# power-mcu.net
KiCad netlist of a schematic drawn in Altium Designer
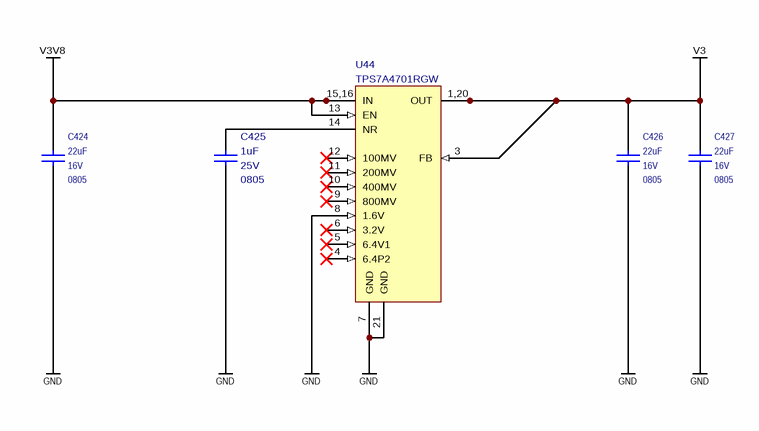
[diagram p0: power-mcu.SchDoc]

(export (version "E")
  (design (tool "Eeschema 10.0.6"))
  (components
    (comp (ref "C424")
      (value "22uF")
      (footprint "generic:CAPC200X125X145L45N")
      (description "Ceramic Capacitor 22uF ±10% 16V X5R 0805")
      (fields
        (field (name "MANUFACTURER") "Samsung")
        (field (name "VOLTAGE") "16V")
        (field (name "PACKAGE") "0805")
        (field (name "TOLERANCE") "±10%")
      )
      (libsource (lib "generic") (part "CAP 0603"))
    )
    (comp (ref "C425")
      (value "1uF")
      (footprint "CAPC200X125X145L45N")
      (description "Ceramic Capacitor 1uF ±10% 25V X7R 0805")
      (fields
        (field (name "MANUFACTURER") "Taiyo Yuden")
        (field (name "TOLERANCE") "±10%")
        (field (name "PACKAGE") "0805")
        (field (name "VOLTAGE") "25V")
      )
      (libsource (lib "capacitors") (part "CAP"))
    )
    (comp (ref "C426")
      (value "22uF")
      (footprint "generic:CAPC200X125X145L45N")
      (description "Ceramic Capacitor 22uF ±10% 16V X5R 0805")
      (fields
        (field (name "MANUFACTURER") "Samsung")
        (field (name "VOLTAGE") "16V")
        (field (name "PACKAGE") "0805")
        (field (name "TOLERANCE") "±10%")
      )
      (libsource (lib "generic") (part "CAP 0603"))
    )
    (comp (ref "C427")
      (value "22uF")
      (footprint "generic:CAPC200X125X145L45N")
      (description "Ceramic Capacitor 22uF ±10% 16V X5R 0805")
      (fields
        (field (name "MANUFACTURER") "Samsung")
        (field (name "VOLTAGE") "16V")
        (field (name "PACKAGE") "0805")
        (field (name "TOLERANCE") "±10%")
      )
      (libsource (lib "generic") (part "CAP 0603"))
    )
    (comp (ref "U44")
      (value "TPS7A4701RGW")
      (footprint "QFN65P500X500X100-21N")
      (description "Low-Dropout Linear Regulator 20-VQFN")
      (fields (field (name "MANUFACTURER") "Texas Instruments"))
      (libsource (lib "ti") (part "TPS7A4701RGW_1"))
    )
  )
  (nets
    (net (code "1") (name "GND") (class "Default")
      (node (ref "C424") (pin "1") (pinfunction "1_1") (pintype "passive"))
      (node (ref "C425") (pin "2") (pinfunction "2_2") (pintype "passive"))
      (node (ref "C426") (pin "1") (pinfunction "1_1") (pintype "passive"))
      (node (ref "C427") (pin "1") (pinfunction "1_1") (pintype "passive"))
      (node (ref "U44") (pin "21") (pinfunction "GND_21") (pintype "power_in"))
      (node (ref "U44") (pin "7") (pinfunction "GND_7") (pintype "power_in"))
      (node (ref "U44") (pin "8") (pinfunction "1.6V_8") (pintype "input"))
    )
    (net (code "2") (name "Net-(U44-NR)") (class "Default")
      (node (ref "C425") (pin "1") (pinfunction "1_1") (pintype "passive"))
      (node (ref "U44") (pin "14") (pinfunction "NR_14") (pintype "passive"))
    )
    (net (code "3") (name "V3") (class "Default")
      (node (ref "C426") (pin "2") (pinfunction "2_2") (pintype "passive"))
      (node (ref "C427") (pin "2") (pinfunction "2_2") (pintype "passive"))
      (node (ref "U44") (pin "1") (pinfunction "OUT_1") (pintype "passive"))
      (node (ref "U44") (pin "20") (pinfunction "OUT_20") (pintype "passive"))
      (node (ref "U44") (pin "3") (pinfunction "FB_3") (pintype "input"))
    )
    (net (code "4") (name "V3V8") (class "Default")
      (node (ref "C424") (pin "2") (pinfunction "2_2") (pintype "passive"))
      (node (ref "U44") (pin "13") (pinfunction "EN_13") (pintype "input"))
      (node (ref "U44") (pin "15") (pinfunction "IN_15") (pintype "passive"))
      (node (ref "U44") (pin "16") (pinfunction "IN_16") (pintype "passive"))
    )
    (net (code "5") (name "unconnected-(U44-3.2V-Pad6)") (class "Default")
      (node (ref "U44") (pin "6") (pinfunction "3.2V_6") (pintype "input+no_connect"))
    )
    (net (code "6") (name "unconnected-(U44-6.4P2-Pad4)") (class "Default")
      (node (ref "U44") (pin "4") (pinfunction "6.4P2_4") (pintype "input+no_connect"))
    )
    (net (code "7") (name "unconnected-(U44-6.4V1-Pad5)") (class "Default")
      (node (ref "U44") (pin "5") (pinfunction "6.4V1_5") (pintype "input+no_connect"))
    )
    (net (code "8") (name "unconnected-(U44-100MV-Pad12)") (class "Default")
      (node (ref "U44") (pin "12") (pinfunction "100MV_12") (pintype "input+no_connect"))
    )
    (net (code "9") (name "unconnected-(U44-200MV-Pad11)") (class "Default")
      (node (ref "U44") (pin "11") (pinfunction "200MV_11") (pintype "input+no_connect"))
    )
    (net (code "10") (name "unconnected-(U44-400MV-Pad10)") (class "Default")
      (node (ref "U44") (pin "10") (pinfunction "400MV_10") (pintype "input+no_connect"))
    )
    (net (code "11") (name "unconnected-(U44-800MV-Pad9)") (class "Default")
      (node (ref "U44") (pin "9") (pinfunction "800MV_9") (pintype "input+no_connect"))
    )
  )
)
